# DS130-1_01-B_G-M.net
KiCad netlist of a schematic drawn in Altium Designer
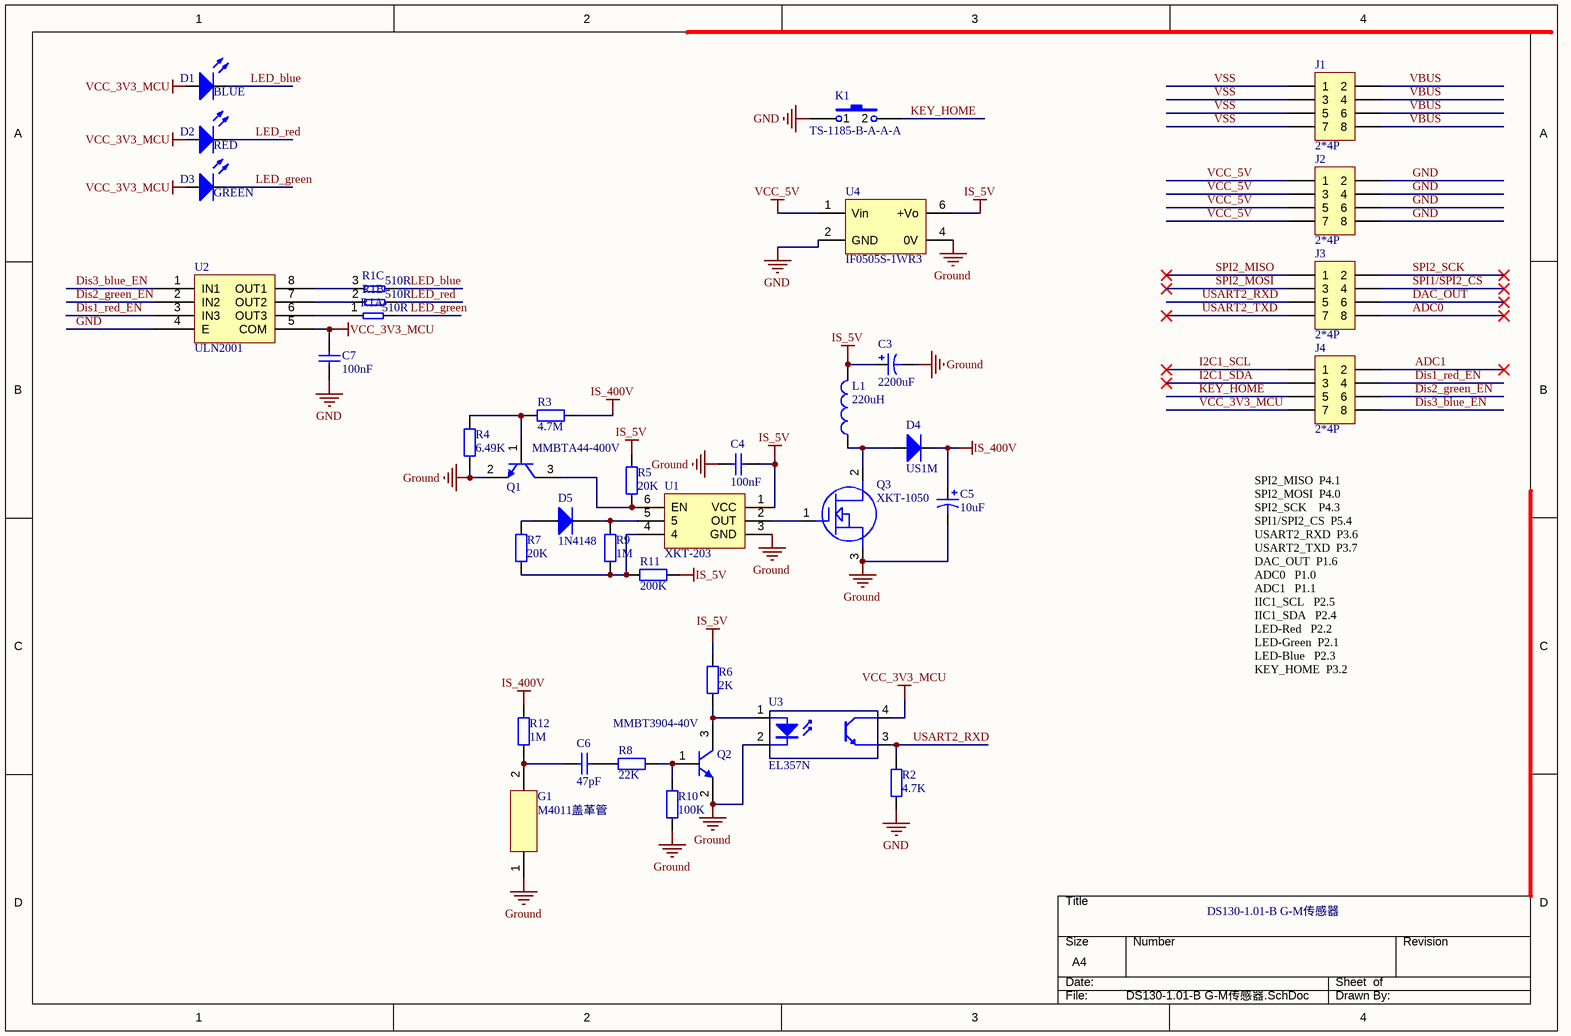
[diagram p0: DS130-1.01-B G-M传感器.SchDoc]

(export (version "E")
  (design (tool "Eeschema 10.0.6"))
  (components
    (comp (ref "C3")
      (value "2200uF")
      (footprint "E-Cap_Ф12.5mm_5mm_DIP")
      (description "插件铝电解电容")
      (fields (field (name "Comment") "E-Cap_2200uF/25V ±20％ 13*21mm DIP2"))
      (libsource (lib "AD_SCH") (part "E-Cap_2200uF/25V ±20％ 13*21mm DIP2"))
    )
    (comp (ref "C4")
      (value "100nF")
      (footprint "0603CAP")
      (description "贴片电容")
      (fields (field (name "Comment") "SMDCAP00013"))
      (libsource (lib "AD_SCH") (part "MLCC 100nF 50V ±10％ 0603"))
    )
    (comp (ref "C5")
      (value "10uF")
      (footprint "E-Cap_Ф10mm_5mm_16mm_DIP")
      (description "插件铝电解电容")
      (fields (field (name "Comment") "E-Cap_10uF/450V ±20％ 4*7mm DIP2"))
      (libsource (lib "AD_SCH") (part "E-Cap_10uF/450V ±20％ 4*7mm DIP2"))
    )
    (comp (ref "C6")
      (value "47pF")
      (footprint "1206CAP")
      (description "贴片电容")
      (fields (field (name "Comment") "MLCC 47pF 1kV ±5％ 1206"))
      (libsource (lib "AD_SCH") (part "MLCC 47pF 1kV ±5％ 1206"))
    )
    (comp (ref "C7")
      (value "100nF")
      (footprint "0603CAP")
      (description "贴片电容")
      (fields (field (name "Comment") "SMDCAP00013"))
      (libsource (lib "AD_SCH") (part "MLCC 100nF 50V ±10％ 0603"))
    )
    (comp (ref "D1")
      (value "BLUE")
      (footprint "LED_0805")
      (description "贴片LED")
      (fields (field (name "Comment") "SMDLED00010"))
      (libsource (lib "AD_SCH") (part "Chip 蓝色LED 0805"))
    )
    (comp (ref "D2")
      (value "RED")
      (footprint "LED_0805")
      (description "贴片LED")
      (fields (field (name "Comment") "SMDLED00003"))
      (libsource (lib "AD_SCH") (part "Chip 红色LED 0805"))
    )
    (comp (ref "D3")
      (value "GREEN")
      (footprint "LED_0805")
      (description "贴片LED")
      (fields (field (name "Comment") "Chip 翠绿LED 0805"))
      (libsource (lib "AD_SCH") (part "Chip 翠绿LED 0805"))
    )
    (comp (ref "D4")
      (value "US1M")
      (footprint "SMA/DO-214AC")
      (description "快恢复/高效率二极管")
      (fields (field (name "Comment") "US1M-DO-214AC"))
      (libsource (lib "AD_SCH") (part "US1M-DO-214AC"))
    )
    (comp (ref "D5")
      (value "1N4148")
      (footprint "SOD-123")
      (description "贴片开关二极管 T4")
      (fields (field (name "Comment") "DIPDIODE02001"))
      (libsource (lib "AD_SCH") (part "1N4148W"))
    )
    (comp (ref "G1") (value "M4011盖革管") (footprint "M4011-90") (libsource (lib "AD_SCH") (part "M4011盖革管")))
    (comp (ref "J1")
      (value "2*4P")
      (footprint "X1321WVS-2x04J-C40D53")
      (description "双排针2x4P 立贴 1.27mm")
      (fields (field (name "Comment") "X1321WVS-2x04J-C40D53"))
      (libsource (lib "AD_SCH") (part "X1321WVS-2x04J-C40D53"))
    )
    (comp (ref "J2")
      (value "2*4P")
      (footprint "X1321WVS-2x04J-C40D53")
      (description "双排针2x4P 立贴 1.27mm")
      (fields (field (name "Comment") "X1321WVS-2x04J-C40D53"))
      (libsource (lib "AD_SCH") (part "X1321WVS-2x04J-C40D53"))
    )
    (comp (ref "J3")
      (value "2*4P")
      (footprint "X1321WVS-2x04J-C40D53")
      (description "双排针2x4P 立贴 1.27mm")
      (fields (field (name "Comment") "X1321WVS-2x04J-C40D53"))
      (libsource (lib "AD_SCH") (part "X1321WVS-2x04J-C40D53"))
    )
    (comp (ref "J4")
      (value "2*4P")
      (footprint "X1321WVS-2x04J-C40D53")
      (description "双排针2x4P 立贴 1.27mm")
      (fields (field (name "Comment") "X1321WVS-2x04J-C40D53"))
      (libsource (lib "AD_SCH") (part "X1321WVS-2x04J-C40D53"))
    )
    (comp (ref "K1")
      (value "TS-1185-B-A-A-A")
      (footprint "KEY_TS-1185-x-A-A-A")
      (description "轻触开关")
      (libsource (lib "AD_SCH") (part "TS-1185-B-A-A-A"))
    )
    (comp (ref "L1")
      (value "220uH")
      (footprint "IND-SMD_L8.0-W8.0")
      (fields (field (name "Comment") "SMD_220uH 8.0*8.0"))
      (libsource (lib "AD_SCH") (part "SMD_220uH 8.0*8.0"))
    )
    (comp (ref "Q1")
      (value "MMBTA44-400V")
      (footprint "SOT23")
      (description "BJT")
      (fields (field (name "Comment") "MMBTA44"))
      (libsource (lib "AD_SCH") (part "MMBTA44"))
    )
    (comp (ref "Q2")
      (value "MMBT3904-40V")
      (footprint "SOT23")
      (description "BJT")
      (fields (field (name "Comment") "MMBT3904"))
      (libsource (lib "AD_SCH") (part "MMBT3904"))
    )
    (comp (ref "Q3")
      (value "XKT-1050")
      (footprint "TO-252")
      (description "NMOS")
      (libsource (lib "AD_SCH") (part "XKT-1050"))
    )
    (comp (ref "R1")
      (value "510R")
      (footprint "0603RES_Pack4")
      (description "贴片排阻")
      (fields (field (name "Comment") "SMDRES05003"))
      (libsource (lib "AD_SCH") (part "Chip R*4 510R 1/16W ±5％ 0603"))
    )
    (comp (ref "R2")
      (value "4.7K")
      (footprint "0603RES")
      (description "贴片电阻")
      (fields (field (name "Comment") "Chip 4.7K 1/16W ±1％ 0603"))
      (libsource (lib "AD_SCH") (part "Chip 4.7K 1/16W ±1％ 0603"))
    )
    (comp (ref "R3")
      (value "4.7M")
      (footprint "1206RES")
      (description "贴片电阻")
      (fields (field (name "Comment") "Chip 4.7M 1/4W ±1％ 1206 500V"))
      (libsource (lib "AD_SCH") (part "Chip 4.7M 1/4W ±1％ 1206 500V"))
    )
    (comp (ref "R4")
      (value "6.49K")
      (footprint "0603RES")
      (description "贴片电阻")
      (fields (field (name "Comment") "Chip 6.49K 1/8W ±1％ 0603"))
      (libsource (lib "AD_SCH") (part "Chip 6.49K 1/8W ±1％ 0603"))
    )
    (comp (ref "R5")
      (value "20K")
      (footprint "0603RES")
      (description "贴片电阻")
      (fields (field (name "Comment") "SMDRES00058"))
      (libsource (lib "AD_SCH") (part "Chip 20K 1/16W ±1％ 0603"))
    )
    (comp (ref "R6")
      (value "2K")
      (footprint "0603RES")
      (description "贴片电阻")
      (fields (field (name "Comment") "SMDRES00042"))
      (libsource (lib "AD_SCH") (part "Chip 2K 1/16W ±1％ 0603"))
    )
    (comp (ref "R7")
      (value "20K")
      (footprint "0603RES")
      (description "贴片电阻")
      (fields (field (name "Comment") "SMDRES00058"))
      (libsource (lib "AD_SCH") (part "Chip 20K 1/16W ±1％ 0603"))
    )
    (comp (ref "R8")
      (value "22K")
      (footprint "0603RES")
      (description "贴片电阻")
      (fields (field (name "Comment") "SMDRES00108"))
      (libsource (lib "AD_SCH") (part "Chip 22K 1/16W ±1％ 0603"))
    )
    (comp (ref "R9")
      (value "1M")
      (footprint "0603RES")
      (description "贴片电阻")
      (fields (field (name "Comment") "SMDRES00085"))
      (libsource (lib "AD_SCH") (part "Chip 1M 1/16W ±1％ 0603"))
    )
    (comp (ref "R10")
      (value "100K")
      (footprint "0603RES")
      (description "贴片电阻")
      (fields (field (name "Comment") "SMDRES00071"))
      (libsource (lib "AD_SCH") (part "Chip 100K 1/16W ±1％ 0603"))
    )
    (comp (ref "R11")
      (value "200K")
      (footprint "0603RES")
      (description "贴片电阻")
      (fields (field (name "Comment") "SMDRES00075"))
      (libsource (lib "AD_SCH") (part "Chip 200K 1/16W ±1％ 0603"))
    )
    (comp (ref "R12")
      (value "1M")
      (footprint "0805RES")
      (description "贴片电阻")
      (fields (field (name "Comment") "Chip 1M 1/10W ±1％ 0805 400V"))
      (libsource (lib "AD_SCH") (part "Chip 1M 1/10W ±1％ 0805 400V"))
    )
    (comp (ref "U1") (value "XKT-203") (footprint "SOT23-6") (libsource (lib "AD_SCH") (part "XKT-203")))
    (comp (ref "U2")
      (value "ULN2001")
      (footprint "SO-8")
      (description "电机驱动芯片")
      (fields (field (name "Comment") "SMDIC000018"))
      (libsource (lib "AD_SCH") (part "ULN2001 SOP-8"))
    )
    (comp (ref "U3")
      (value "EL357N")
      (footprint "SO-4")
      (description "光耦")
      (libsource (lib "AD_SCH") (part "EL357N"))
    )
    (comp (ref "U4")
      (value "IF0505S-1WR3")
      (footprint "IF0505S-1WR3")
      (libsource (lib "AD_SCH") (part "IF0505S-1WR3"))
    )
  )
  (nets
    (net (code "1") (name "/ADC0") (class "Default")
      (node (ref "J3") (pin "8") (pinfunction "8_8") (pintype "passive+no_connect"))
    )
    (net (code "2") (name "/ADC1") (class "Default")
      (node (ref "J4") (pin "2") (pinfunction "2_2") (pintype "passive+no_connect"))
    )
    (net (code "3") (name "/DAC_OUT") (class "Default")
      (node (ref "J3") (pin "6") (pinfunction "6_6") (pintype "passive+no_connect"))
    )
    (net (code "4") (name "/Dis1_red_EN") (class "Default")
      (node (ref "J4") (pin "4") (pinfunction "4_4") (pintype "passive"))
      (node (ref "U2") (pin "3") (pinfunction "IN3_3") (pintype "passive"))
    )
    (net (code "5") (name "/Dis2_green_EN") (class "Default")
      (node (ref "J4") (pin "6") (pinfunction "6_6") (pintype "passive"))
      (node (ref "U2") (pin "2") (pinfunction "IN2_2") (pintype "passive"))
    )
    (net (code "6") (name "/Dis3_blue_EN") (class "Default")
      (node (ref "J4") (pin "8") (pinfunction "8_8") (pintype "passive"))
      (node (ref "U2") (pin "1") (pinfunction "IN1_1") (pintype "passive"))
    )
    (net (code "7") (name "/I2C1_SCL") (class "Default")
      (node (ref "J4") (pin "1") (pinfunction "1_1") (pintype "passive+no_connect"))
    )
    (net (code "8") (name "/I2C1_SDA") (class "Default")
      (node (ref "J4") (pin "3") (pinfunction "3_3") (pintype "passive+no_connect"))
    )
    (net (code "9") (name "/KEY_HOME") (class "Default")
      (node (ref "J4") (pin "5") (pinfunction "5_5") (pintype "passive"))
      (node (ref "K1") (pin "2") (pinfunction "2_2") (pintype "passive"))
    )
    (net (code "10") (name "/LED_blue") (class "Default")
      (node (ref "D1") (pin "2") (pinfunction "K_2") (pintype "passive"))
      (node (ref "R1") (pin "6") (pinfunction "6_6") (pintype "passive"))
    )
    (net (code "11") (name "/LED_green") (class "Default")
      (node (ref "D3") (pin "2") (pinfunction "K_2") (pintype "passive"))
      (node (ref "R1") (pin "8") (pinfunction "8_8") (pintype "passive"))
    )
    (net (code "12") (name "/LED_red") (class "Default")
      (node (ref "D2") (pin "2") (pinfunction "K_2") (pintype "passive"))
      (node (ref "R1") (pin "7") (pinfunction "7_7") (pintype "passive"))
    )
    (net (code "13") (name "/SPI1{slash}SPI2_CS") (class "Default")
      (node (ref "J3") (pin "4") (pinfunction "4_4") (pintype "passive+no_connect"))
    )
    (net (code "14") (name "/SPI2_MISO") (class "Default")
      (node (ref "J3") (pin "1") (pinfunction "1_1") (pintype "passive+no_connect"))
    )
    (net (code "15") (name "/SPI2_MOSI") (class "Default")
      (node (ref "J3") (pin "3") (pinfunction "3_3") (pintype "passive+no_connect"))
    )
    (net (code "16") (name "/SPI2_SCK") (class "Default")
      (node (ref "J3") (pin "2") (pinfunction "2_2") (pintype "passive+no_connect"))
    )
    (net (code "17") (name "/USART2_RXD") (class "Default")
      (node (ref "J3") (pin "5") (pinfunction "5_5") (pintype "passive"))
      (node (ref "R2") (pin "2") (pinfunction "2_2") (pintype "passive"))
      (node (ref "U3") (pin "3") (pinfunction "E_3") (pintype "passive"))
    )
    (net (code "18") (name "/USART2_TXD") (class "Default")
      (node (ref "J3") (pin "7") (pinfunction "7_7") (pintype "passive+no_connect"))
    )
    (net (code "19") (name "/VBUS") (class "Default")
      (node (ref "J1") (pin "2") (pinfunction "2_2") (pintype "passive"))
      (node (ref "J1") (pin "4") (pinfunction "4_4") (pintype "passive"))
      (node (ref "J1") (pin "6") (pinfunction "6_6") (pintype "passive"))
      (node (ref "J1") (pin "8") (pinfunction "8_8") (pintype "passive"))
    )
    (net (code "20") (name "/VSS") (class "Default")
      (node (ref "J1") (pin "1") (pinfunction "1_1") (pintype "passive"))
      (node (ref "J1") (pin "3") (pinfunction "3_3") (pintype "passive"))
      (node (ref "J1") (pin "5") (pinfunction "5_5") (pintype "passive"))
      (node (ref "J1") (pin "7") (pinfunction "7_7") (pintype "passive"))
    )
    (net (code "21") (name "GND") (class "Default")
      (node (ref "C7") (pin "2") (pinfunction "2_2") (pintype "passive"))
      (node (ref "J2") (pin "2") (pinfunction "2_2") (pintype "passive"))
      (node (ref "J2") (pin "4") (pinfunction "4_4") (pintype "passive"))
      (node (ref "J2") (pin "6") (pinfunction "6_6") (pintype "passive"))
      (node (ref "J2") (pin "8") (pinfunction "8_8") (pintype "passive"))
      (node (ref "K1") (pin "1") (pinfunction "1_1") (pintype "passive"))
      (node (ref "R2") (pin "1") (pinfunction "1_1") (pintype "passive"))
      (node (ref "U2") (pin "4") (pinfunction "E_4") (pintype "passive"))
      (node (ref "U4") (pin "2") (pinfunction "GND_2") (pintype "passive"))
    )
    (net (code "22") (name "Ground") (class "Default")
      (node (ref "C3") (pin "2") (pinfunction "2_2") (pintype "passive"))
      (node (ref "C4") (pin "1") (pinfunction "1_1") (pintype "passive"))
      (node (ref "C5") (pin "2") (pinfunction "2_2") (pintype "passive"))
      (node (ref "G1") (pin "1") (pinfunction "1_1") (pintype "passive"))
      (node (ref "Q1") (pin "2") (pinfunction "E_2") (pintype "passive"))
      (node (ref "Q2") (pin "2") (pinfunction "E_2") (pintype "passive"))
      (node (ref "Q3") (pin "3") (pinfunction "S_3") (pintype "passive"))
      (node (ref "R10") (pin "1") (pinfunction "1_1") (pintype "passive"))
      (node (ref "R4") (pin "1") (pinfunction "1_1") (pintype "passive"))
      (node (ref "U1") (pin "3") (pinfunction "GND_3") (pintype "passive"))
      (node (ref "U3") (pin "2") (pinfunction "K_2") (pintype "passive"))
      (node (ref "U4") (pin "4") (pinfunction "0V_4") (pintype "passive"))
    )
    (net (code "23") (name "IS_5V") (class "Default")
      (node (ref "C3") (pin "1") (pinfunction "1_1") (pintype "passive"))
      (node (ref "C4") (pin "2") (pinfunction "2_2") (pintype "passive"))
      (node (ref "L1") (pin "2") (pinfunction "2_2") (pintype "passive"))
      (node (ref "R11") (pin "1") (pinfunction "1_1") (pintype "passive"))
      (node (ref "R5") (pin "2") (pinfunction "2_2") (pintype "passive"))
      (node (ref "R6") (pin "2") (pinfunction "2_2") (pintype "passive"))
      (node (ref "U1") (pin "1") (pinfunction "VCC_1") (pintype "passive"))
      (node (ref "U4") (pin "6") (pinfunction "+Vo_6") (pintype "passive"))
    )
    (net (code "24") (name "IS_400V") (class "Default")
      (node (ref "C5") (pin "1") (pinfunction "1_1") (pintype "passive"))
      (node (ref "D4") (pin "2") (pinfunction "K_2") (pintype "passive"))
      (node (ref "R12") (pin "2") (pinfunction "2_2") (pintype "passive"))
      (node (ref "R3") (pin "2") (pinfunction "2_2") (pintype "passive"))
    )
    (net (code "25") (name "Net-(C6-Pad1)") (class "Default")
      (node (ref "C6") (pin "1") (pinfunction "1_1") (pintype "passive"))
      (node (ref "G1") (pin "2") (pinfunction "2_2") (pintype "passive"))
      (node (ref "R12") (pin "1") (pinfunction "1_1") (pintype "passive"))
    )
    (net (code "26") (name "Net-(C6-Pad2)") (class "Default")
      (node (ref "C6") (pin "2") (pinfunction "2_2") (pintype "passive"))
      (node (ref "R8") (pin "1") (pinfunction "1_1") (pintype "passive"))
    )
    (net (code "27") (name "Net-(D4-A)") (class "Default")
      (node (ref "D4") (pin "1") (pinfunction "A_1") (pintype "passive"))
      (node (ref "L1") (pin "1") (pinfunction "1_1") (pintype "passive"))
      (node (ref "Q3") (pin "2") (pinfunction "D_2") (pintype "passive"))
    )
    (net (code "28") (name "Net-(D5-A)") (class "Default")
      (node (ref "D5") (pin "1") (pinfunction "A_1") (pintype "passive"))
      (node (ref "R7") (pin "2") (pinfunction "2_2") (pintype "passive"))
    )
    (net (code "29") (name "Net-(D5-K)") (class "Default")
      (node (ref "D5") (pin "2") (pinfunction "K_2") (pintype "passive"))
      (node (ref "R9") (pin "2") (pinfunction "2_2") (pintype "passive"))
      (node (ref "U1") (pin "5") (pinfunction "5_5") (pintype "passive"))
    )
    (net (code "30") (name "Net-(Q1-B)") (class "Default")
      (node (ref "Q1") (pin "1") (pinfunction "B_1") (pintype "passive"))
      (node (ref "R3") (pin "1") (pinfunction "1_1") (pintype "passive"))
      (node (ref "R4") (pin "2") (pinfunction "2_2") (pintype "passive"))
    )
    (net (code "31") (name "Net-(Q1-C)") (class "Default")
      (node (ref "Q1") (pin "3") (pinfunction "C_3") (pintype "passive"))
      (node (ref "R5") (pin "1") (pinfunction "1_1") (pintype "passive"))
      (node (ref "U1") (pin "6") (pinfunction "EN_6") (pintype "passive"))
    )
    (net (code "32") (name "Net-(Q2-B)") (class "Default")
      (node (ref "Q2") (pin "1") (pinfunction "B_1") (pintype "passive"))
      (node (ref "R10") (pin "2") (pinfunction "2_2") (pintype "passive"))
      (node (ref "R8") (pin "2") (pinfunction "2_2") (pintype "passive"))
    )
    (net (code "33") (name "Net-(Q2-C)") (class "Default")
      (node (ref "Q2") (pin "3") (pinfunction "C_3") (pintype "passive"))
      (node (ref "R6") (pin "1") (pinfunction "1_1") (pintype "passive"))
      (node (ref "U3") (pin "1") (pinfunction "A_1") (pintype "passive"))
    )
    (net (code "34") (name "Net-(Q3-G)") (class "Default")
      (node (ref "Q3") (pin "1") (pinfunction "G_1") (pintype "passive"))
      (node (ref "U1") (pin "2") (pinfunction "OUT_2") (pintype "passive"))
    )
    (net (code "35") (name "Net-(R11-Pad2)") (class "Default")
      (node (ref "R11") (pin "2") (pinfunction "2_2") (pintype "passive"))
      (node (ref "R7") (pin "1") (pinfunction "1_1") (pintype "passive"))
      (node (ref "R9") (pin "1") (pinfunction "1_1") (pintype "passive"))
      (node (ref "U1") (pin "4") (pinfunction "4_4") (pintype "passive"))
    )
    (net (code "36") (name "Net-(U2-OUT1)") (class "Default")
      (node (ref "R1") (pin "3") (pinfunction "3_3") (pintype "passive"))
      (node (ref "U2") (pin "8") (pinfunction "OUT1_8") (pintype "passive"))
    )
    (net (code "37") (name "Net-(U2-OUT2)") (class "Default")
      (node (ref "R1") (pin "2") (pinfunction "2_2") (pintype "passive"))
      (node (ref "U2") (pin "7") (pinfunction "OUT2_7") (pintype "passive"))
    )
    (net (code "38") (name "Net-(U2-OUT3)") (class "Default")
      (node (ref "R1") (pin "1") (pinfunction "1_1") (pintype "passive"))
      (node (ref "U2") (pin "6") (pinfunction "OUT3_6") (pintype "passive"))
    )
    (net (code "39") (name "VCC_3V3_MCU") (class "Default")
      (node (ref "C7") (pin "1") (pinfunction "1_1") (pintype "passive"))
      (node (ref "D1") (pin "1") (pinfunction "A_1") (pintype "passive"))
      (node (ref "D2") (pin "1") (pinfunction "A_1") (pintype "passive"))
      (node (ref "D3") (pin "1") (pinfunction "A_1") (pintype "passive"))
      (node (ref "J4") (pin "7") (pinfunction "7_7") (pintype "passive"))
      (node (ref "U2") (pin "5") (pinfunction "COM_5") (pintype "passive"))
      (node (ref "U3") (pin "4") (pinfunction "C_4") (pintype "passive"))
    )
    (net (code "40") (name "VCC_5V") (class "Default")
      (node (ref "J2") (pin "1") (pinfunction "1_1") (pintype "passive"))
      (node (ref "J2") (pin "3") (pinfunction "3_3") (pintype "passive"))
      (node (ref "J2") (pin "5") (pinfunction "5_5") (pintype "passive"))
      (node (ref "J2") (pin "7") (pinfunction "7_7") (pintype "passive"))
      (node (ref "U4") (pin "1") (pinfunction "Vin_1") (pintype "passive"))
    )
  )
)
